# Wiegand.net
KiCad netlist of a schematic drawn in EAGLE
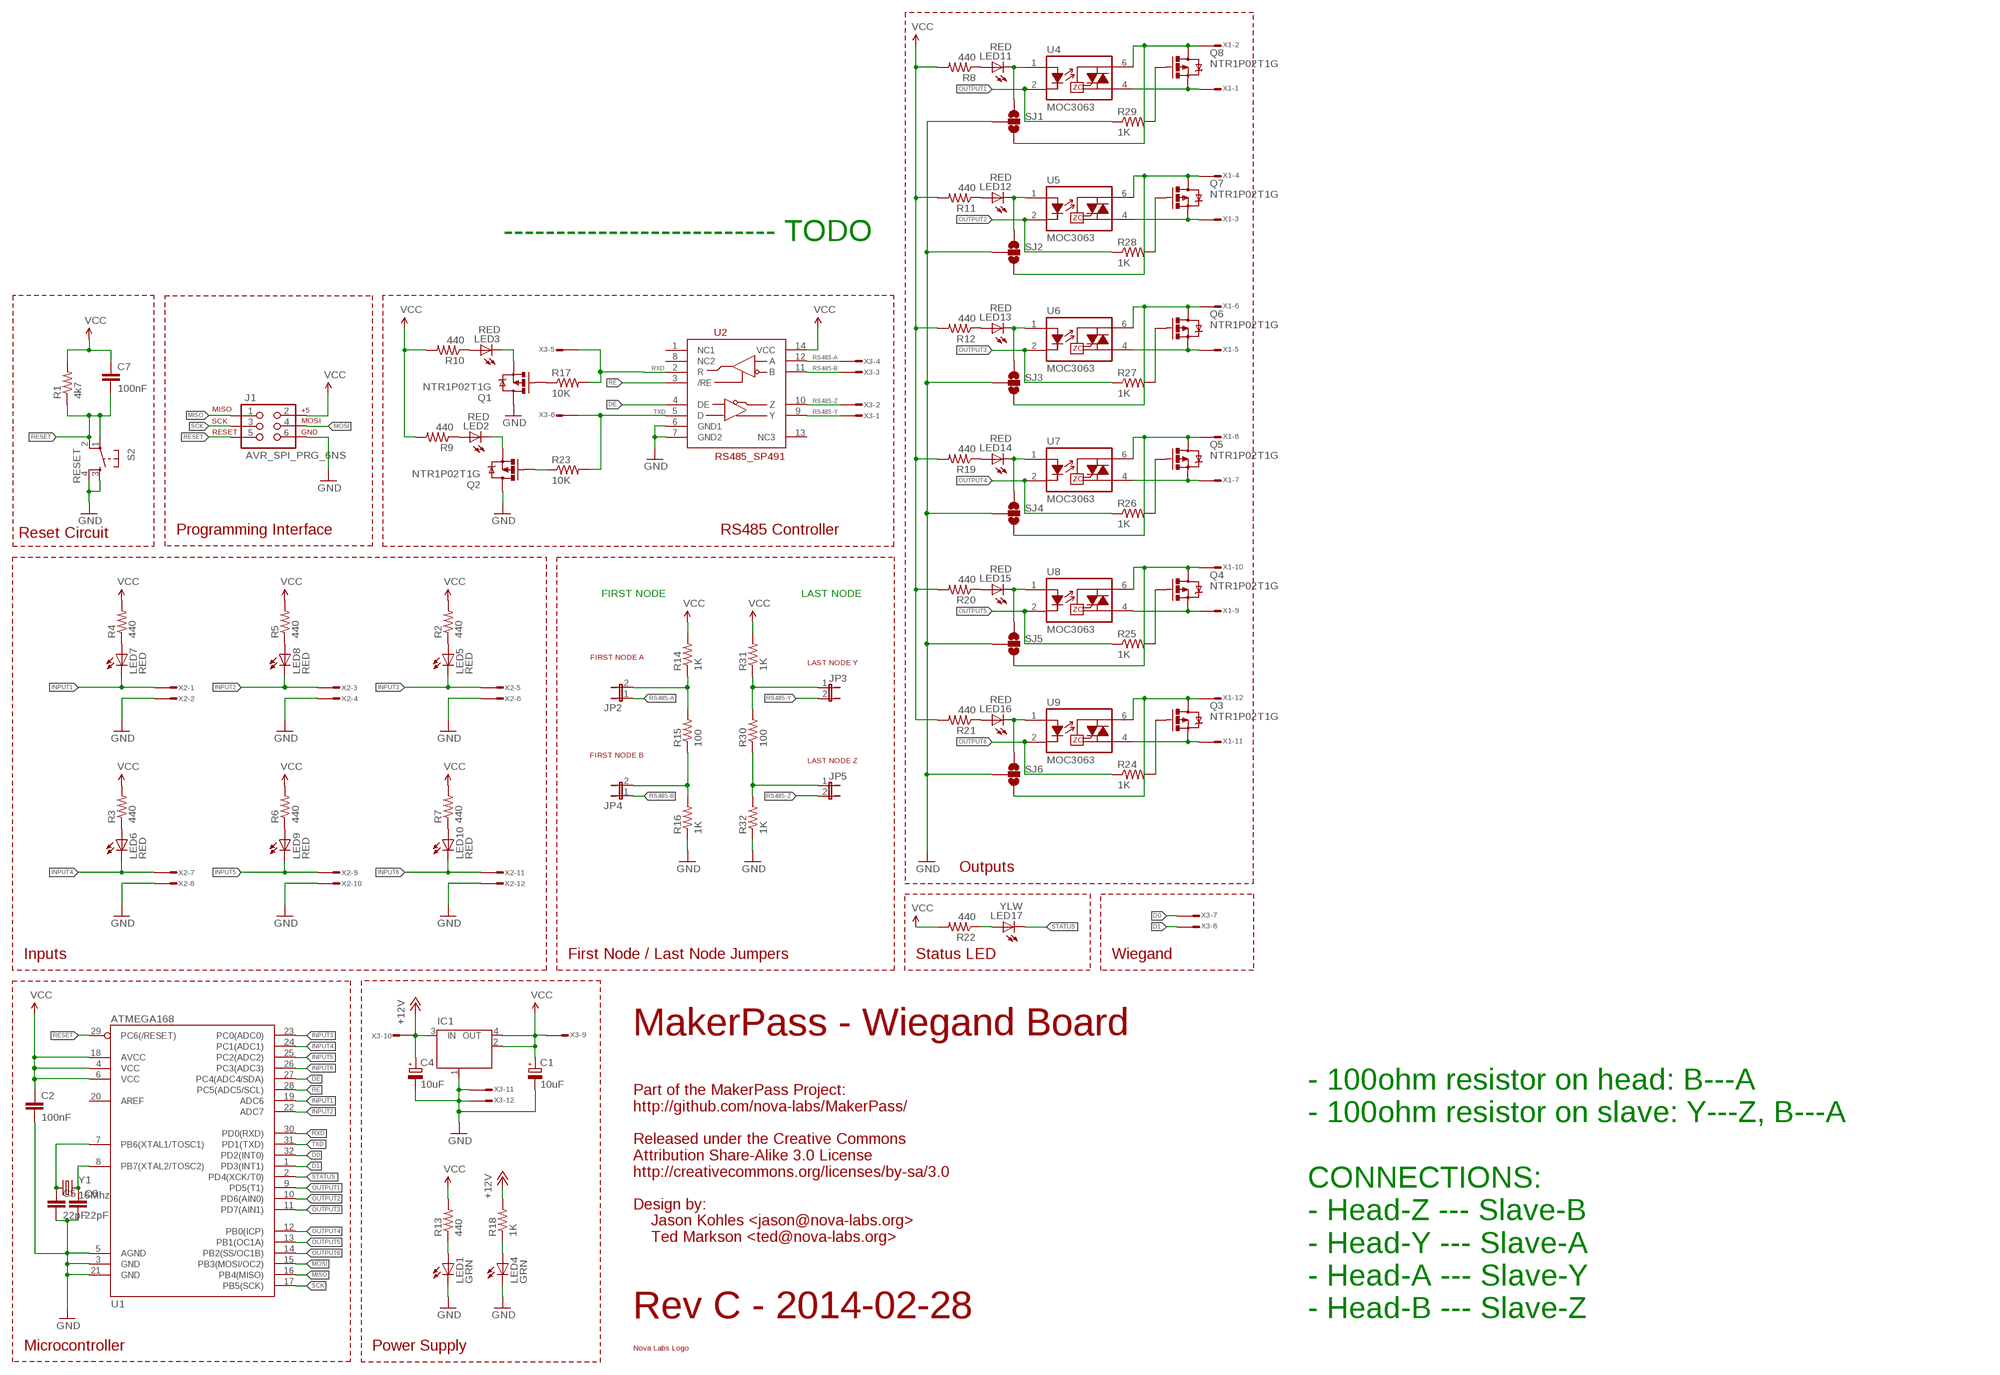
[diagram p0: schematic, sheet 1]

(export (version "E")
  (design (tool "Eeschema 10.0.6"))
  (components
    (comp (ref "C1")
      (value "10uF")
      (footprint "eagle-import:PANASONIC_D")
      (libsource (lib "eagle-import") (part "CPOL-EUD"))
    )
    (comp (ref "C2")
      (value "100nF")
      (footprint "eagle-import:0603-CAP")
      (libsource (lib "eagle-import") (part "CAP0603-CAP"))
    )
    (comp (ref "C4")
      (value "10uF")
      (footprint "eagle-import:PANASONIC_D")
      (libsource (lib "eagle-import") (part "CPOL-EUD"))
    )
    (comp (ref "C5")
      (value "22pF")
      (footprint "eagle-import:0603-CAP")
      (libsource (lib "eagle-import") (part "CAP0603-CAP"))
    )
    (comp (ref "C6")
      (value "22pF")
      (footprint "eagle-import:0603-CAP")
      (libsource (lib "eagle-import") (part "CAP0603-CAP"))
    )
    (comp (ref "C7")
      (value "100nF")
      (footprint "eagle-import:0603-CAP")
      (libsource (lib "eagle-import") (part "CAP0603-CAP"))
    )
    (comp (ref "IC1")
      (value "MC33269ST-3.3T3")
      (footprint "eagle-import:SOT223")
      (libsource (lib "eagle-import") (part "MC33269ST-3.3T3"))
    )
    (comp (ref "J1")
      (value "AVR_SPI_PRG_6NS")
      (footprint "eagle-import:2X3-NS")
      (libsource (lib "eagle-import") (part "AVR_SPI_PRG_6NS"))
    )
    (comp (ref "JP2")
      (value "JUMPER-2PTH")
      (footprint "eagle-import:1X02")
      (libsource (lib "eagle-import") (part "JUMPER-2PTH"))
    )
    (comp (ref "JP3")
      (value "JUMPER-2PTH")
      (footprint "eagle-import:1X02")
      (libsource (lib "eagle-import") (part "JUMPER-2PTH"))
    )
    (comp (ref "JP4")
      (value "JUMPER-2PTH")
      (footprint "eagle-import:1X02")
      (libsource (lib "eagle-import") (part "JUMPER-2PTH"))
    )
    (comp (ref "JP5")
      (value "JUMPER-2PTH")
      (footprint "eagle-import:1X02")
      (libsource (lib "eagle-import") (part "JUMPER-2PTH"))
    )
    (comp (ref "LED1")
      (value "GRN")
      (footprint "eagle-import:LED-805")
      (libsource (lib "eagle-import") (part "LED-0805"))
    )
    (comp (ref "LED2")
      (value "RED")
      (footprint "eagle-import:LED-805")
      (libsource (lib "eagle-import") (part "LED-0805"))
    )
    (comp (ref "LED3")
      (value "RED")
      (footprint "eagle-import:LED-805")
      (libsource (lib "eagle-import") (part "LED-0805"))
    )
    (comp (ref "LED4")
      (value "GRN")
      (footprint "eagle-import:LED-805")
      (libsource (lib "eagle-import") (part "LED-0805"))
    )
    (comp (ref "LED5")
      (value "RED")
      (footprint "eagle-import:LED-805")
      (libsource (lib "eagle-import") (part "LED-0805"))
    )
    (comp (ref "LED6")
      (value "RED")
      (footprint "eagle-import:LED-805")
      (libsource (lib "eagle-import") (part "LED-0805"))
    )
    (comp (ref "LED7")
      (value "RED")
      (footprint "eagle-import:LED-805")
      (libsource (lib "eagle-import") (part "LED-0805"))
    )
    (comp (ref "LED8")
      (value "RED")
      (footprint "eagle-import:LED-805")
      (libsource (lib "eagle-import") (part "LED-0805"))
    )
    (comp (ref "LED9")
      (value "RED")
      (footprint "eagle-import:LED-805")
      (libsource (lib "eagle-import") (part "LED-0805"))
    )
    (comp (ref "LED10")
      (value "RED")
      (footprint "eagle-import:LED-805")
      (libsource (lib "eagle-import") (part "LED-0805"))
    )
    (comp (ref "LED11")
      (value "RED")
      (footprint "eagle-import:LED-805")
      (libsource (lib "eagle-import") (part "LED-0805"))
    )
    (comp (ref "LED12")
      (value "RED")
      (footprint "eagle-import:LED-805")
      (libsource (lib "eagle-import") (part "LED-0805"))
    )
    (comp (ref "LED13")
      (value "RED")
      (footprint "eagle-import:LED-805")
      (libsource (lib "eagle-import") (part "LED-0805"))
    )
    (comp (ref "LED14")
      (value "RED")
      (footprint "eagle-import:LED-805")
      (libsource (lib "eagle-import") (part "LED-0805"))
    )
    (comp (ref "LED15")
      (value "RED")
      (footprint "eagle-import:LED-805")
      (libsource (lib "eagle-import") (part "LED-0805"))
    )
    (comp (ref "LED16")
      (value "RED")
      (footprint "eagle-import:LED-805")
      (libsource (lib "eagle-import") (part "LED-0805"))
    )
    (comp (ref "LED17")
      (value "YLW")
      (footprint "eagle-import:LED-805")
      (libsource (lib "eagle-import") (part "LED-0805"))
    )
    (comp (ref "Q1")
      (value "NTR1P02T1G")
      (footprint "eagle-import:SOT23-3")
      (libsource (lib "eagle-import") (part "MOSFET-PCHANNELSMD"))
    )
    (comp (ref "Q2")
      (value "NTR1P02T1G")
      (footprint "eagle-import:SOT23-3")
      (libsource (lib "eagle-import") (part "MOSFET-PCHANNELSMD"))
    )
    (comp (ref "Q3")
      (value "NTR1P02T1G")
      (footprint "eagle-import:SOT23-3")
      (libsource (lib "eagle-import") (part "MOSFET-PCHANNELSMD"))
    )
    (comp (ref "Q4")
      (value "NTR1P02T1G")
      (footprint "eagle-import:SOT23-3")
      (libsource (lib "eagle-import") (part "MOSFET-PCHANNELSMD"))
    )
    (comp (ref "Q5")
      (value "NTR1P02T1G")
      (footprint "eagle-import:SOT23-3")
      (libsource (lib "eagle-import") (part "MOSFET-PCHANNELSMD"))
    )
    (comp (ref "Q6")
      (value "NTR1P02T1G")
      (footprint "eagle-import:SOT23-3")
      (libsource (lib "eagle-import") (part "MOSFET-PCHANNELSMD"))
    )
    (comp (ref "Q7")
      (value "NTR1P02T1G")
      (footprint "eagle-import:SOT23-3")
      (libsource (lib "eagle-import") (part "MOSFET-PCHANNELSMD"))
    )
    (comp (ref "Q8")
      (value "NTR1P02T1G")
      (footprint "eagle-import:SOT23-3")
      (libsource (lib "eagle-import") (part "MOSFET-PCHANNELSMD"))
    )
    (comp (ref "R1")
      (value "4k7")
      (footprint "eagle-import:0603-RES")
      (libsource (lib "eagle-import") (part "RESISTOR0603-RES"))
    )
    (comp (ref "R2")
      (value "440")
      (footprint "eagle-import:0603-RES")
      (libsource (lib "eagle-import") (part "RESISTOR0603-RES"))
    )
    (comp (ref "R3")
      (value "440")
      (footprint "eagle-import:0603-RES")
      (libsource (lib "eagle-import") (part "RESISTOR0603-RES"))
    )
    (comp (ref "R4")
      (value "440")
      (footprint "eagle-import:0603-RES")
      (libsource (lib "eagle-import") (part "RESISTOR0603-RES"))
    )
    (comp (ref "R5")
      (value "440")
      (footprint "eagle-import:0603-RES")
      (libsource (lib "eagle-import") (part "RESISTOR0603-RES"))
    )
    (comp (ref "R6")
      (value "440")
      (footprint "eagle-import:0603-RES")
      (libsource (lib "eagle-import") (part "RESISTOR0603-RES"))
    )
    (comp (ref "R7")
      (value "440")
      (footprint "eagle-import:0603-RES")
      (libsource (lib "eagle-import") (part "RESISTOR0603-RES"))
    )
    (comp (ref "R8")
      (value "440")
      (footprint "eagle-import:0603-RES")
      (libsource (lib "eagle-import") (part "RESISTOR0603-RES"))
    )
    (comp (ref "R9")
      (value "440")
      (footprint "eagle-import:0603-RES")
      (libsource (lib "eagle-import") (part "RESISTOR0603-RES"))
    )
    (comp (ref "R10")
      (value "440")
      (footprint "eagle-import:0603-RES")
      (libsource (lib "eagle-import") (part "RESISTOR0603-RES"))
    )
    (comp (ref "R11")
      (value "440")
      (footprint "eagle-import:0603-RES")
      (libsource (lib "eagle-import") (part "RESISTOR0603-RES"))
    )
    (comp (ref "R12")
      (value "440")
      (footprint "eagle-import:0603-RES")
      (libsource (lib "eagle-import") (part "RESISTOR0603-RES"))
    )
    (comp (ref "R13")
      (value "440")
      (footprint "eagle-import:0603-RES")
      (libsource (lib "eagle-import") (part "RESISTOR0603-RES"))
    )
    (comp (ref "R14")
      (value "1K")
      (footprint "eagle-import:0603-RES")
      (libsource (lib "eagle-import") (part "RESISTOR0603-RES"))
    )
    (comp (ref "R15")
      (value "100")
      (footprint "eagle-import:0603-RES")
      (libsource (lib "eagle-import") (part "RESISTOR0603-RES"))
    )
    (comp (ref "R16")
      (value "1K")
      (footprint "eagle-import:0603-RES")
      (libsource (lib "eagle-import") (part "RESISTOR0603-RES"))
    )
    (comp (ref "R17")
      (value "10K")
      (footprint "eagle-import:0603-RES")
      (libsource (lib "eagle-import") (part "RESISTOR0603-RES"))
    )
    (comp (ref "R18")
      (value "1K")
      (footprint "eagle-import:0603-RES")
      (libsource (lib "eagle-import") (part "RESISTOR0603-RES"))
    )
    (comp (ref "R19")
      (value "440")
      (footprint "eagle-import:0603-RES")
      (libsource (lib "eagle-import") (part "RESISTOR0603-RES"))
    )
    (comp (ref "R20")
      (value "440")
      (footprint "eagle-import:0603-RES")
      (libsource (lib "eagle-import") (part "RESISTOR0603-RES"))
    )
    (comp (ref "R21")
      (value "440")
      (footprint "eagle-import:0603-RES")
      (libsource (lib "eagle-import") (part "RESISTOR0603-RES"))
    )
    (comp (ref "R22")
      (value "440")
      (footprint "eagle-import:0603-RES")
      (libsource (lib "eagle-import") (part "RESISTOR0603-RES"))
    )
    (comp (ref "R23")
      (value "10K")
      (footprint "eagle-import:0603-RES")
      (libsource (lib "eagle-import") (part "RESISTOR0603-RES"))
    )
    (comp (ref "R24")
      (value "1K")
      (footprint "eagle-import:0603-RES")
      (libsource (lib "eagle-import") (part "RESISTOR0603-RES"))
    )
    (comp (ref "R25")
      (value "1K")
      (footprint "eagle-import:0603-RES")
      (libsource (lib "eagle-import") (part "RESISTOR0603-RES"))
    )
    (comp (ref "R26")
      (value "1K")
      (footprint "eagle-import:0603-RES")
      (libsource (lib "eagle-import") (part "RESISTOR0603-RES"))
    )
    (comp (ref "R27")
      (value "1K")
      (footprint "eagle-import:0603-RES")
      (libsource (lib "eagle-import") (part "RESISTOR0603-RES"))
    )
    (comp (ref "R28")
      (value "1K")
      (footprint "eagle-import:0603-RES")
      (libsource (lib "eagle-import") (part "RESISTOR0603-RES"))
    )
    (comp (ref "R29")
      (value "1K")
      (footprint "eagle-import:0603-RES")
      (libsource (lib "eagle-import") (part "RESISTOR0603-RES"))
    )
    (comp (ref "R30")
      (value "100")
      (footprint "eagle-import:0603-RES")
      (libsource (lib "eagle-import") (part "RESISTOR0603-RES"))
    )
    (comp (ref "R31")
      (value "1K")
      (footprint "eagle-import:0603-RES")
      (libsource (lib "eagle-import") (part "RESISTOR0603-RES"))
    )
    (comp (ref "R32")
      (value "1K")
      (footprint "eagle-import:0603-RES")
      (libsource (lib "eagle-import") (part "RESISTOR0603-RES"))
    )
    (comp (ref "S2")
      (value "RESET")
      (footprint "eagle-import:TACTILE_SWITCH_SMD")
      (libsource (lib "eagle-import") (part "TAC_SWITCHSMD"))
    )
    (comp (ref "SJ1")
      (value "SOLDERJUMPER_2WAY-TRACE1&2&3")
      (footprint "eagle-import:SJ_3_WIRE1&2&3")
      (libsource (lib "eagle-import") (part "SOLDERJUMPER_2WAY-TRACE1&2&3"))
    )
    (comp (ref "SJ2")
      (value "SOLDERJUMPER_2WAY-TRACE1&2&3")
      (footprint "eagle-import:SJ_3_WIRE1&2&3")
      (libsource (lib "eagle-import") (part "SOLDERJUMPER_2WAY-TRACE1&2&3"))
    )
    (comp (ref "SJ3")
      (value "SOLDERJUMPER_2WAY-TRACE1&2&3")
      (footprint "eagle-import:SJ_3_WIRE1&2&3")
      (libsource (lib "eagle-import") (part "SOLDERJUMPER_2WAY-TRACE1&2&3"))
    )
    (comp (ref "SJ4")
      (value "SOLDERJUMPER_2WAY-TRACE1&2&3")
      (footprint "eagle-import:SJ_3_WIRE1&2&3")
      (libsource (lib "eagle-import") (part "SOLDERJUMPER_2WAY-TRACE1&2&3"))
    )
    (comp (ref "SJ5")
      (value "SOLDERJUMPER_2WAY-TRACE1&2&3")
      (footprint "eagle-import:SJ_3_WIRE1&2&3")
      (libsource (lib "eagle-import") (part "SOLDERJUMPER_2WAY-TRACE1&2&3"))
    )
    (comp (ref "SJ6")
      (value "SOLDERJUMPER_2WAY-TRACE1&2&3")
      (footprint "eagle-import:SJ_3_WIRE1&2&3")
      (libsource (lib "eagle-import") (part "SOLDERJUMPER_2WAY-TRACE1&2&3"))
    )
    (comp (ref "U1")
      (value "ATMEGA168")
      (footprint "eagle-import:TQFP32-08")
      (libsource (lib "eagle-import") (part "ATMEGA168"))
    )
    (comp (ref "U2")
      (value "RS485_SP491")
      (footprint "eagle-import:SOIC-14")
      (libsource (lib "eagle-import") (part "RS485_SP491"))
    )
    (comp (ref "U4")
      (value "MOC3063")
      (footprint "eagle-import:DIP8SMD")
      (libsource (lib "eagle-import") (part "MOC3063S"))
    )
    (comp (ref "U5")
      (value "MOC3063")
      (footprint "eagle-import:DIP8SMD")
      (libsource (lib "eagle-import") (part "MOC3063S"))
    )
    (comp (ref "U6")
      (value "MOC3063")
      (footprint "eagle-import:DIP8SMD")
      (libsource (lib "eagle-import") (part "MOC3063S"))
    )
    (comp (ref "U7")
      (value "MOC3063")
      (footprint "eagle-import:DIP8SMD")
      (libsource (lib "eagle-import") (part "MOC3063S"))
    )
    (comp (ref "U8")
      (value "MOC3063")
      (footprint "eagle-import:DIP8SMD")
      (libsource (lib "eagle-import") (part "MOC3063S"))
    )
    (comp (ref "U9")
      (value "MOC3063")
      (footprint "eagle-import:DIP8SMD")
      (libsource (lib "eagle-import") (part "MOC3063S"))
    )
    (comp (ref "X1")
      (value "CON-1X12-TERMBLOCK-3.5MM")
      (footprint "eagle-import:CON-1X12-TERMBLOCK-3.5MM")
      (fields (field (name "MFG_PN") "OSTTE120104"))
      (libsource (lib "eagle-import") (part "CON-1X12-TERMBLOCK-3.5MM"))
    )
    (comp (ref "X2")
      (value "CON-1X12-TERMBLOCK-3.5MM")
      (footprint "eagle-import:CON-1X12-TERMBLOCK-3.5MM")
      (fields (field (name "MFG_PN") "OSTTE120104"))
      (libsource (lib "eagle-import") (part "CON-1X12-TERMBLOCK-3.5MM"))
    )
    (comp (ref "X3")
      (value "CON-1X12-TERMBLOCK-3.5MM")
      (footprint "eagle-import:CON-1X12-TERMBLOCK-3.5MM")
      (fields (field (name "MFG_PN") "OSTTE120104"))
      (libsource (lib "eagle-import") (part "CON-1X12-TERMBLOCK-3.5MM"))
    )
    (comp (ref "X4")
      (value "NOVA-LABS-LOGO-SILK-400MIL")
      (footprint "eagle-import:NOVA-LABS-LOGO-SILK-400MIL")
      (libsource (lib "eagle-import") (part "NOVA-LABS-LOGO-SILK-400MIL"))
    )
    (comp (ref "Y1")
      (value "16Mhz")
      (footprint "eagle-import:HC49UP")
      (libsource (lib "eagle-import") (part "CRYSTALSMD"))
    )
  )
  (nets
    (net (code "1") (name "+12V") (class "Default")
      (node (ref "C4") (pin "+") (pinfunction "+_+") (pintype "passive"))
      (node (ref "IC1") (pin "3") (pinfunction "IN_3") (pintype "input"))
      (node (ref "R18") (pin "2") (pinfunction "2_2") (pintype "passive"))
      (node (ref "X3") (pin "10") (pinfunction "S_10") (pintype "passive"))
    )
    (net (code "2") (name "D0") (class "Default")
      (node (ref "U1") (pin "32") (pinfunction "PD2(INT0)_32") (pintype "bidirectional"))
      (node (ref "X3") (pin "7") (pinfunction "S_7") (pintype "passive"))
    )
    (net (code "3") (name "D1") (class "Default")
      (node (ref "U1") (pin "1") (pinfunction "PD3(INT1)_1") (pintype "bidirectional"))
      (node (ref "X3") (pin "8") (pinfunction "S_8") (pintype "passive"))
    )
    (net (code "4") (name "DE") (class "Default")
      (node (ref "U1") (pin "27") (pinfunction "PC4(ADC4/SDA)_27") (pintype "bidirectional"))
      (node (ref "U2") (pin "4") (pinfunction "DE_4") (pintype "bidirectional"))
    )
    (net (code "5") (name "GND") (class "Default")
      (node (ref "C1") (pin "-") (pinfunction "-_-") (pintype "passive"))
      (node (ref "C2") (pin "2") (pinfunction "2_2") (pintype "passive"))
      (node (ref "C4") (pin "-") (pinfunction "-_-") (pintype "passive"))
      (node (ref "C5") (pin "2") (pinfunction "2_2") (pintype "passive"))
      (node (ref "C6") (pin "2") (pinfunction "2_2") (pintype "passive"))
      (node (ref "IC1") (pin "1") (pinfunction "GND/ADJ_1") (pintype "input"))
      (node (ref "J1") (pin "6") (pinfunction "6_6") (pintype "passive"))
      (node (ref "LED1") (pin "C") (pinfunction "C_C") (pintype "passive"))
      (node (ref "LED4") (pin "C") (pinfunction "C_C") (pintype "passive"))
      (node (ref "Q1") (pin "3") (pinfunction "D_3") (pintype "passive"))
      (node (ref "Q2") (pin "3") (pinfunction "D_3") (pintype "passive"))
      (node (ref "R16") (pin "1") (pinfunction "1_1") (pintype "passive"))
      (node (ref "R32") (pin "1") (pinfunction "1_1") (pintype "passive"))
      (node (ref "S2") (pin "3") (pinfunction "3_3") (pintype "passive"))
      (node (ref "S2") (pin "4") (pinfunction "4_4") (pintype "passive"))
      (node (ref "SJ1") (pin "2") (pinfunction "2_2") (pintype "passive"))
      (node (ref "SJ2") (pin "2") (pinfunction "2_2") (pintype "passive"))
      (node (ref "SJ3") (pin "2") (pinfunction "2_2") (pintype "passive"))
      (node (ref "SJ4") (pin "2") (pinfunction "2_2") (pintype "passive"))
      (node (ref "SJ5") (pin "2") (pinfunction "2_2") (pintype "passive"))
      (node (ref "SJ6") (pin "2") (pinfunction "2_2") (pintype "passive"))
      (node (ref "U1") (pin "21") (pinfunction "GND_21") (pintype "bidirectional"))
      (node (ref "U1") (pin "3") (pinfunction "GND_3") (pintype "bidirectional"))
      (node (ref "U1") (pin "5") (pinfunction "AGND_5") (pintype "bidirectional"))
      (node (ref "U2") (pin "6") (pinfunction "GND1_6") (pintype "bidirectional"))
      (node (ref "U2") (pin "7") (pinfunction "GND2_7") (pintype "bidirectional"))
      (node (ref "X2") (pin "10") (pinfunction "S_10") (pintype "passive"))
      (node (ref "X2") (pin "12") (pinfunction "S_12") (pintype "passive"))
      (node (ref "X2") (pin "2") (pinfunction "S_2") (pintype "passive"))
      (node (ref "X2") (pin "4") (pinfunction "S_4") (pintype "passive"))
      (node (ref "X2") (pin "6") (pinfunction "S_6") (pintype "passive"))
      (node (ref "X2") (pin "8") (pinfunction "S_8") (pintype "passive"))
      (node (ref "X3") (pin "11") (pinfunction "S_11") (pintype "passive"))
      (node (ref "X3") (pin "12") (pinfunction "S_12") (pintype "passive"))
    )
    (net (code "6") (name "INPUT1") (class "Default")
      (node (ref "LED7") (pin "C") (pinfunction "C_C") (pintype "passive"))
      (node (ref "U1") (pin "19") (pinfunction "ADC6_19") (pintype "bidirectional"))
      (node (ref "X2") (pin "1") (pinfunction "S_1") (pintype "passive"))
    )
    (net (code "7") (name "INPUT2") (class "Default")
      (node (ref "LED8") (pin "C") (pinfunction "C_C") (pintype "passive"))
      (node (ref "U1") (pin "22") (pinfunction "ADC7_22") (pintype "bidirectional"))
      (node (ref "X2") (pin "3") (pinfunction "S_3") (pintype "passive"))
    )
    (net (code "8") (name "INPUT3") (class "Default")
      (node (ref "LED5") (pin "C") (pinfunction "C_C") (pintype "passive"))
      (node (ref "U1") (pin "23") (pinfunction "PC0(ADC0)_23") (pintype "bidirectional"))
      (node (ref "X2") (pin "5") (pinfunction "S_5") (pintype "passive"))
    )
    (net (code "9") (name "INPUT4") (class "Default")
      (node (ref "LED6") (pin "C") (pinfunction "C_C") (pintype "passive"))
      (node (ref "U1") (pin "24") (pinfunction "PC1(ADC1)_24") (pintype "bidirectional"))
      (node (ref "X2") (pin "7") (pinfunction "S_7") (pintype "passive"))
    )
    (net (code "10") (name "INPUT5") (class "Default")
      (node (ref "LED9") (pin "C") (pinfunction "C_C") (pintype "passive"))
      (node (ref "U1") (pin "25") (pinfunction "PC2(ADC2)_25") (pintype "bidirectional"))
      (node (ref "X2") (pin "9") (pinfunction "S_9") (pintype "passive"))
    )
    (net (code "11") (name "INPUT6") (class "Default")
      (node (ref "LED10") (pin "C") (pinfunction "C_C") (pintype "passive"))
      (node (ref "U1") (pin "26") (pinfunction "PC3(ADC3)_26") (pintype "bidirectional"))
      (node (ref "X2") (pin "11") (pinfunction "S_11") (pintype "passive"))
    )
    (net (code "12") (name "MISO") (class "Default")
      (node (ref "J1") (pin "1") (pinfunction "1_1") (pintype "passive"))
      (node (ref "U1") (pin "16") (pinfunction "PB4(MISO)_16") (pintype "bidirectional"))
    )
    (net (code "13") (name "MOSI") (class "Default")
      (node (ref "J1") (pin "4") (pinfunction "4_4") (pintype "passive"))
      (node (ref "U1") (pin "15") (pinfunction "PB3(MOSI/OC2)_15") (pintype "bidirectional"))
    )
    (net (code "14") (name "Net-(JP2-Pad2)") (class "Default")
      (node (ref "JP2") (pin "2") (pinfunction "2_2") (pintype "passive"))
      (node (ref "R14") (pin "1") (pinfunction "1_1") (pintype "passive"))
      (node (ref "R15") (pin "2") (pinfunction "2_2") (pintype "passive"))
    )
    (net (code "15") (name "Net-(JP3-Pad1)") (class "Default")
      (node (ref "JP3") (pin "1") (pinfunction "1_1") (pintype "passive"))
      (node (ref "R30") (pin "2") (pinfunction "2_2") (pintype "passive"))
      (node (ref "R31") (pin "1") (pinfunction "1_1") (pintype "passive"))
    )
    (net (code "16") (name "Net-(JP4-Pad2)") (class "Default")
      (node (ref "JP4") (pin "2") (pinfunction "2_2") (pintype "passive"))
      (node (ref "R15") (pin "1") (pinfunction "1_1") (pintype "passive"))
      (node (ref "R16") (pin "2") (pinfunction "2_2") (pintype "passive"))
    )
    (net (code "17") (name "Net-(JP5-Pad1)") (class "Default")
      (node (ref "JP5") (pin "1") (pinfunction "1_1") (pintype "passive"))
      (node (ref "R30") (pin "1") (pinfunction "1_1") (pintype "passive"))
      (node (ref "R32") (pin "2") (pinfunction "2_2") (pintype "passive"))
    )
    (net (code "18") (name "Net-(LED1-PadA)") (class "Default")
      (node (ref "LED1") (pin "A") (pinfunction "A_A") (pintype "passive"))
      (node (ref "R13") (pin "1") (pinfunction "1_1") (pintype "passive"))
    )
    (net (code "19") (name "Net-(LED2-PadA)") (class "Default")
      (node (ref "LED2") (pin "A") (pinfunction "A_A") (pintype "passive"))
      (node (ref "R9") (pin "1") (pinfunction "1_1") (pintype "passive"))
    )
    (net (code "20") (name "Net-(LED3-PadA)") (class "Default")
      (node (ref "LED3") (pin "A") (pinfunction "A_A") (pintype "passive"))
      (node (ref "R10") (pin "1") (pinfunction "1_1") (pintype "passive"))
    )
    (net (code "21") (name "Net-(LED4-PadA)") (class "Default")
      (node (ref "LED4") (pin "A") (pinfunction "A_A") (pintype "passive"))
      (node (ref "R18") (pin "1") (pinfunction "1_1") (pintype "passive"))
    )
    (net (code "22") (name "Net-(LED5-PadA)") (class "Default")
      (node (ref "LED5") (pin "A") (pinfunction "A_A") (pintype "passive"))
      (node (ref "R2") (pin "1") (pinfunction "1_1") (pintype "passive"))
    )
    (net (code "23") (name "Net-(LED6-PadA)") (class "Default")
      (node (ref "LED6") (pin "A") (pinfunction "A_A") (pintype "passive"))
      (node (ref "R3") (pin "1") (pinfunction "1_1") (pintype "passive"))
    )
    (net (code "24") (name "Net-(LED7-PadA)") (class "Default")
      (node (ref "LED7") (pin "A") (pinfunction "A_A") (pintype "passive"))
      (node (ref "R4") (pin "1") (pinfunction "1_1") (pintype "passive"))
    )
    (net (code "25") (name "Net-(LED8-PadA)") (class "Default")
      (node (ref "LED8") (pin "A") (pinfunction "A_A") (pintype "passive"))
      (node (ref "R5") (pin "1") (pinfunction "1_1") (pintype "passive"))
    )
    (net (code "26") (name "Net-(LED9-PadA)") (class "Default")
      (node (ref "LED9") (pin "A") (pinfunction "A_A") (pintype "passive"))
      (node (ref "R6") (pin "1") (pinfunction "1_1") (pintype "passive"))
    )
    (net (code "27") (name "Net-(LED10-PadA)") (class "Default")
      (node (ref "LED10") (pin "A") (pinfunction "A_A") (pintype "passive"))
      (node (ref "R7") (pin "1") (pinfunction "1_1") (pintype "passive"))
    )
    (net (code "28") (name "Net-(LED11-PadA)") (class "Default")
      (node (ref "LED11") (pin "A") (pinfunction "A_A") (pintype "passive"))
      (node (ref "R8") (pin "1") (pinfunction "1_1") (pintype "passive"))
    )
    (net (code "29") (name "Net-(LED12-PadA)") (class "Default")
      (node (ref "LED12") (pin "A") (pinfunction "A_A") (pintype "passive"))
      (node (ref "R11") (pin "1") (pinfunction "1_1") (pintype "passive"))
    )
    (net (code "30") (name "Net-(LED13-PadA)") (class "Default")
      (node (ref "LED13") (pin "A") (pinfunction "A_A") (pintype "passive"))
      (node (ref "R12") (pin "1") (pinfunction "1_1") (pintype "passive"))
    )
    (net (code "31") (name "Net-(LED14-PadA)") (class "Default")
      (node (ref "LED14") (pin "A") (pinfunction "A_A") (pintype "passive"))
      (node (ref "R19") (pin "1") (pinfunction "1_1") (pintype "passive"))
    )
    (net (code "32") (name "Net-(LED15-PadA)") (class "Default")
      (node (ref "LED15") (pin "A") (pinfunction "A_A") (pintype "passive"))
      (node (ref "R20") (pin "1") (pinfunction "1_1") (pintype "passive"))
    )
    (net (code "33") (name "Net-(LED16-PadA)") (class "Default")
      (node (ref "LED16") (pin "A") (pinfunction "A_A") (pintype "passive"))
      (node (ref "R21") (pin "1") (pinfunction "1_1") (pintype "passive"))
    )
    (net (code "34") (name "Net-(LED17-PadA)") (class "Default")
      (node (ref "LED17") (pin "A") (pinfunction "A_A") (pintype "passive"))
      (node (ref "R22") (pin "1") (pinfunction "1_1") (pintype "passive"))
    )
    (net (code "35") (name "Net-(Q1-G)") (class "Default")
      (node (ref "Q1") (pin "1") (pinfunction "G_1") (pintype "passive"))
      (node (ref "R17") (pin "1") (pinfunction "1_1") (pintype "passive"))
    )
    (net (code "36") (name "Net-(Q1-S)") (class "Default")
      (node (ref "LED3") (pin "C") (pinfunction "C_C") (pintype "passive"))
      (node (ref "Q1") (pin "2") (pinfunction "S_2") (pintype "passive"))
    )
    (net (code "37") (name "Net-(Q2-G)") (class "Default")
      (node (ref "Q2") (pin "1") (pinfunction "G_1") (pintype "passive"))
      (node (ref "R23") (pin "1") (pinfunction "1_1") (pintype "passive"))
    )
    (net (code "38") (name "Net-(Q2-S)") (class "Default")
      (node (ref "LED2") (pin "C") (pinfunction "C_C") (pintype "passive"))
      (node (ref "Q2") (pin "2") (pinfunction "S_2") (pintype "passive"))
    )
    (net (code "39") (name "Net-(Q3-D)") (class "Default")
      (node (ref "Q3") (pin "3") (pinfunction "D_3") (pintype "passive"))
      (node (ref "SJ6") (pin "3") (pinfunction "3_3") (pintype "passive"))
      (node (ref "U9") (pin "6") (pinfunction "T1_6") (pintype "bidirectional"))
      (node (ref "X1") (pin "12") (pinfunction "S_12") (pintype "passive"))
    )
    (net (code "40") (name "Net-(Q3-G)") (class "Default")
      (node (ref "Q3") (pin "1") (pinfunction "G_1") (pintype "passive"))
      (node (ref "R24") (pin "2") (pinfunction "2_2") (pintype "passive"))
    )
    (net (code "41") (name "Net-(Q3-S)") (class "Default")
      (node (ref "Q3") (pin "2") (pinfunction "S_2") (pintype "passive"))
      (node (ref "U9") (pin "4") (pinfunction "T2_4") (pintype "bidirectional"))
      (node (ref "X1") (pin "11") (pinfunction "S_11") (pintype "passive"))
    )
    (net (code "42") (name "Net-(Q4-D)") (class "Default")
      (node (ref "Q4") (pin "3") (pinfunction "D_3") (pintype "passive"))
      (node (ref "SJ5") (pin "3") (pinfunction "3_3") (pintype "passive"))
      (node (ref "U8") (pin "6") (pinfunction "T1_6") (pintype "bidirectional"))
      (node (ref "X1") (pin "10") (pinfunction "S_10") (pintype "passive"))
    )
    (net (code "43") (name "Net-(Q4-G)") (class "Default")
      (node (ref "Q4") (pin "1") (pinfunction "G_1") (pintype "passive"))
      (node (ref "R25") (pin "2") (pinfunction "2_2") (pintype "passive"))
    )
    (net (code "44") (name "Net-(Q4-S)") (class "Default")
      (node (ref "Q4") (pin "2") (pinfunction "S_2") (pintype "passive"))
      (node (ref "U8") (pin "4") (pinfunction "T2_4") (pintype "bidirectional"))
      (node (ref "X1") (pin "9") (pinfunction "S_9") (pintype "passive"))
    )
    (net (code "45") (name "Net-(Q5-D)") (class "Default")
      (node (ref "Q5") (pin "3") (pinfunction "D_3") (pintype "passive"))
      (node (ref "SJ4") (pin "3") (pinfunction "3_3") (pintype "passive"))
      (node (ref "U7") (pin "6") (pinfunction "T1_6") (pintype "bidirectional"))
      (node (ref "X1") (pin "8") (pinfunction "S_8") (pintype "passive"))
    )
    (net (code "46") (name "Net-(Q5-G)") (class "Default")
      (node (ref "Q5") (pin "1") (pinfunction "G_1") (pintype "passive"))
      (node (ref "R26") (pin "2") (pinfunction "2_2") (pintype "passive"))
    )
    (net (code "47") (name "Net-(Q5-S)") (class "Default")
      (node (ref "Q5") (pin "2") (pinfunction "S_2") (pintype "passive"))
      (node (ref "U7") (pin "4") (pinfunction "T2_4") (pintype "bidirectional"))
      (node (ref "X1") (pin "7") (pinfunction "S_7") (pintype "passive"))
    )
    (net (code "48") (name "Net-(Q6-D)") (class "Default")
      (node (ref "Q6") (pin "3") (pinfunction "D_3") (pintype "passive"))
      (node (ref "SJ3") (pin "3") (pinfunction "3_3") (pintype "passive"))
      (node (ref "U6") (pin "6") (pinfunction "T1_6") (pintype "bidirectional"))
      (node (ref "X1") (pin "6") (pinfunction "S_6") (pintype "passive"))
    )
    (net (code "49") (name "Net-(Q6-G)") (class "Default")
      (node (ref "Q6") (pin "1") (pinfunction "G_1") (pintype "passive"))
      (node (ref "R27") (pin "2") (pinfunction "2_2") (pintype "passive"))
    )
    (net (code "50") (name "Net-(Q6-S)") (class "Default")
      (node (ref "Q6") (pin "2") (pinfunction "S_2") (pintype "passive"))
      (node (ref "U6") (pin "4") (pinfunction "T2_4") (pintype "bidirectional"))
      (node (ref "X1") (pin "5") (pinfunction "S_5") (pintype "passive"))
    )
    (net (code "51") (name "Net-(Q7-D)") (class "Default")
      (node (ref "Q7") (pin "3") (pinfunction "D_3") (pintype "passive"))
      (node (ref "SJ2") (pin "3") (pinfunction "3_3") (pintype "passive"))
      (node (ref "U5") (pin "6") (pinfunction "T1_6") (pintype "bidirectional"))
      (node (ref "X1") (pin "4") (pinfunction "S_4") (pintype "passive"))
    )
    (net (code "52") (name "Net-(Q7-G)") (class "Default")
      (node (ref "Q7") (pin "1") (pinfunction "G_1") (pintype "passive"))
      (node (ref "R28") (pin "2") (pinfunction "2_2") (pintype "passive"))
    )
    (net (code "53") (name "Net-(Q7-S)") (class "Default")
      (node (ref "Q7") (pin "2") (pinfunction "S_2") (pintype "passive"))
      (node (ref "U5") (pin "4") (pinfunction "T2_4") (pintype "bidirectional"))
      (node (ref "X1") (pin "3") (pinfunction "S_3") (pintype "passive"))
    )
    (net (code "54") (name "Net-(Q8-D)") (class "Default")
      (node (ref "Q8") (pin "3") (pinfunction "D_3") (pintype "passive"))
      (node (ref "SJ1") (pin "3") (pinfunction "3_3") (pintype "passive"))
      (node (ref "U4") (pin "6") (pinfunction "T1_6") (pintype "bidirectional"))
      (node (ref "X1") (pin "2") (pinfunction "S_2") (pintype "passive"))
    )
    (net (code "55") (name "Net-(Q8-G)") (class "Default")
      (node (ref "Q8") (pin "1") (pinfunction "G_1") (pintype "passive"))
      (node (ref "R29") (pin "2") (pinfunction "2_2") (pintype "passive"))
    )
    (net (code "56") (name "Net-(Q8-S)") (class "Default")
      (node (ref "Q8") (pin "2") (pinfunction "S_2") (pintype "passive"))
      (node (ref "U4") (pin "4") (pinfunction "T2_4") (pintype "bidirectional"))
      (node (ref "X1") (pin "1") (pinfunction "S_1") (pintype "passive"))
    )
    (net (code "57") (name "Net-(U1-PB6(XTAL1{slash}TOSC1))") (class "Default")
      (node (ref "C5") (pin "1") (pinfunction "1_1") (pintype "passive"))
      (node (ref "U1") (pin "7") (pinfunction "PB6(XTAL1/TOSC1)_7") (pintype "bidirectional"))
      (node (ref "Y1") (pin "1") (pinfunction "1_1") (pintype "passive"))
    )
    (net (code "58") (name "Net-(U1-PB7(XTAL2{slash}TOSC2))") (class "Default")
      (node (ref "C6") (pin "1") (pinfunction "1_1") (pintype "passive"))
      (node (ref "U1") (pin "8") (pinfunction "PB7(XTAL2/TOSC2)_8") (pintype "bidirectional"))
      (node (ref "Y1") (pin "2") (pinfunction "2_2") (pintype "passive"))
    )
    (net (code "59") (name "Net-(U4-A)") (class "Default")
      (node (ref "LED11") (pin "C") (pinfunction "C_C") (pintype "passive"))
      (node (ref "SJ1") (pin "1") (pinfunction "1_1") (pintype "passive"))
      (node (ref "U4") (pin "1") (pinfunction "A_1") (pintype "bidirectional"))
    )
    (net (code "60") (name "Net-(U5-A)") (class "Default")
      (node (ref "LED12") (pin "C") (pinfunction "C_C") (pintype "passive"))
      (node (ref "SJ2") (pin "1") (pinfunction "1_1") (pintype "passive"))
      (node (ref "U5") (pin "1") (pinfunction "A_1") (pintype "bidirectional"))
    )
    (net (code "61") (name "Net-(U6-A)") (class "Default")
      (node (ref "LED13") (pin "C") (pinfunction "C_C") (pintype "passive"))
      (node (ref "SJ3") (pin "1") (pinfunction "1_1") (pintype "passive"))
      (node (ref "U6") (pin "1") (pinfunction "A_1") (pintype "bidirectional"))
    )
    (net (code "62") (name "Net-(U7-A)") (class "Default")
      (node (ref "LED14") (pin "C") (pinfunction "C_C") (pintype "passive"))
      (node (ref "SJ4") (pin "1") (pinfunction "1_1") (pintype "passive"))
      (node (ref "U7") (pin "1") (pinfunction "A_1") (pintype "bidirectional"))
    )
    (net (code "63") (name "Net-(U8-A)") (class "Default")
      (node (ref "LED15") (pin "C") (pinfunction "C_C") (pintype "passive"))
      (node (ref "SJ5") (pin "1") (pinfunction "1_1") (pintype "passive"))
      (node (ref "U8") (pin "1") (pinfunction "A_1") (pintype "bidirectional"))
    )
    (net (code "64") (name "Net-(U9-A)") (class "Default")
      (node (ref "LED16") (pin "C") (pinfunction "C_C") (pintype "passive"))
      (node (ref "SJ6") (pin "1") (pinfunction "1_1") (pintype "passive"))
      (node (ref "U9") (pin "1") (pinfunction "A_1") (pintype "bidirectional"))
    )
    (net (code "65") (name "OUTPUT1") (class "Default")
      (node (ref "R29") (pin "1") (pinfunction "1_1") (pintype "passive"))
      (node (ref "U1") (pin "9") (pinfunction "PD5(T1)_9") (pintype "bidirectional"))
      (node (ref "U4") (pin "2") (pinfunction "K_2") (pintype "bidirectional"))
    )
    (net (code "66") (name "OUTPUT2") (class "Default")
      (node (ref "R28") (pin "1") (pinfunction "1_1") (pintype "passive"))
      (node (ref "U1") (pin "10") (pinfunction "PD6(AIN0)_10") (pintype "bidirectional"))
      (node (ref "U5") (pin "2") (pinfunction "K_2") (pintype "bidirectional"))
    )
    (net (code "67") (name "OUTPUT3") (class "Default")
      (node (ref "R27") (pin "1") (pinfunction "1_1") (pintype "passive"))
      (node (ref "U1") (pin "11") (pinfunction "PD7(AIN1)_11") (pintype "bidirectional"))
      (node (ref "U6") (pin "2") (pinfunction "K_2") (pintype "bidirectional"))
    )
    (net (code "68") (name "OUTPUT4") (class "Default")
      (node (ref "R26") (pin "1") (pinfunction "1_1") (pintype "passive"))
      (node (ref "U1") (pin "12") (pinfunction "PB0(ICP)_12") (pintype "bidirectional"))
      (node (ref "U7") (pin "2") (pinfunction "K_2") (pintype "bidirectional"))
    )
    (net (code "69") (name "OUTPUT5") (class "Default")
      (node (ref "R25") (pin "1") (pinfunction "1_1") (pintype "passive"))
      (node (ref "U1") (pin "13") (pinfunction "PB1(OC1A)_13") (pintype "bidirectional"))
      (node (ref "U8") (pin "2") (pinfunction "K_2") (pintype "bidirectional"))
    )
    (net (code "70") (name "OUTPUT6") (class "Default")
      (node (ref "R24") (pin "1") (pinfunction "1_1") (pintype "passive"))
      (node (ref "U1") (pin "14") (pinfunction "PB2(SS/OC1B)_14") (pintype "bidirectional"))
      (node (ref "U9") (pin "2") (pinfunction "K_2") (pintype "bidirectional"))
    )
    (net (code "71") (name "RE") (class "Default")
      (node (ref "U1") (pin "28") (pinfunction "PC5(ADC5/SCL)_28") (pintype "bidirectional"))
      (node (ref "U2") (pin "3") (pinfunction "/RE_3") (pintype "bidirectional"))
    )
    (net (code "72") (name "RESET") (class "Default")
      (node (ref "C7") (pin "2") (pinfunction "2_2") (pintype "passive"))
      (node (ref "J1") (pin "5") (pinfunction "5_5") (pintype "passive"))
      (node (ref "R1") (pin "1") (pinfunction "1_1") (pintype "passive"))
      (node (ref "S2") (pin "1") (pinfunction "1_1") (pintype "passive"))
      (node (ref "S2") (pin "2") (pinfunction "2_2") (pintype "passive"))
      (node (ref "U1") (pin "29") (pinfunction "PC6(/RESET)_29") (pintype "bidirectional"))
    )
    (net (code "73") (name "RS485-A") (class "Default")
      (node (ref "JP2") (pin "1") (pinfunction "1_1") (pintype "passive"))
      (node (ref "U2") (pin "12") (pinfunction "A_12") (pintype "bidirectional"))
      (node (ref "X3") (pin "4") (pinfunction "S_4") (pintype "passive"))
    )
    (net (code "74") (name "RS485-B") (class "Default")
      (node (ref "JP4") (pin "1") (pinfunction "1_1") (pintype "passive"))
      (node (ref "U2") (pin "11") (pinfunction "B_11") (pintype "bidirectional"))
      (node (ref "X3") (pin "3") (pinfunction "S_3") (pintype "passive"))
    )
    (net (code "75") (name "RS485-Y") (class "Default")
      (node (ref "JP3") (pin "2") (pinfunction "2_2") (pintype "passive"))
      (node (ref "U2") (pin "9") (pinfunction "Y_9") (pintype "bidirectional"))
      (node (ref "X3") (pin "1") (pinfunction "S_1") (pintype "passive"))
    )
    (net (code "76") (name "RS485-Z") (class "Default")
      (node (ref "JP5") (pin "2") (pinfunction "2_2") (pintype "passive"))
      (node (ref "U2") (pin "10") (pinfunction "Z_10") (pintype "bidirectional"))
      (node (ref "X3") (pin "2") (pinfunction "S_2") (pintype "passive"))
    )
    (net (code "77") (name "RXD") (class "Default")
      (node (ref "R17") (pin "2") (pinfunction "2_2") (pintype "passive"))
      (node (ref "U1") (pin "30") (pinfunction "PD0(RXD)_30") (pintype "bidirectional"))
      (node (ref "U2") (pin "2") (pinfunction "R_2") (pintype "bidirectional"))
      (node (ref "X3") (pin "5") (pinfunction "S_5") (pintype "passive"))
    )
    (net (code "78") (name "SCK") (class "Default")
      (node (ref "J1") (pin "3") (pinfunction "3_3") (pintype "passive"))
      (node (ref "U1") (pin "17") (pinfunction "PB5(SCK)_17") (pintype "bidirectional"))
    )
    (net (code "79") (name "STATUS") (class "Default")
      (node (ref "LED17") (pin "C") (pinfunction "C_C") (pintype "passive"))
      (node (ref "U1") (pin "2") (pinfunction "PD4(XCK/T0)_2") (pintype "bidirectional"))
    )
    (net (code "80") (name "TXD") (class "Default")
      (node (ref "R23") (pin "2") (pinfunction "2_2") (pintype "passive"))
      (node (ref "U1") (pin "31") (pinfunction "PD1(TXD)_31") (pintype "bidirectional"))
      (node (ref "U2") (pin "5") (pinfunction "D_5") (pintype "bidirectional"))
      (node (ref "X3") (pin "6") (pinfunction "S_6") (pintype "passive"))
    )
    (net (code "81") (name "VCC") (class "Default")
      (node (ref "C1") (pin "+") (pinfunction "+_+") (pintype "passive"))
      (node (ref "C2") (pin "1") (pinfunction "1_1") (pintype "passive"))
      (node (ref "C7") (pin "1") (pinfunction "1_1") (pintype "passive"))
      (node (ref "IC1") (pin "2") (pinfunction "OUT_2") (pintype "passive"))
      (node (ref "IC1") (pin "4") (pinfunction "OUT_4") (pintype "passive"))
      (node (ref "J1") (pin "2") (pinfunction "2_2") (pintype "passive"))
      (node (ref "R1") (pin "2") (pinfunction "2_2") (pintype "passive"))
      (node (ref "R10") (pin "2") (pinfunction "2_2") (pintype "passive"))
      (node (ref "R11") (pin "2") (pinfunction "2_2") (pintype "passive"))
      (node (ref "R12") (pin "2") (pinfunction "2_2") (pintype "passive"))
      (node (ref "R13") (pin "2") (pinfunction "2_2") (pintype "passive"))
      (node (ref "R14") (pin "2") (pinfunction "2_2") (pintype "passive"))
      (node (ref "R19") (pin "2") (pinfunction "2_2") (pintype "passive"))
      (node (ref "R2") (pin "2") (pinfunction "2_2") (pintype "passive"))
      (node (ref "R20") (pin "2") (pinfunction "2_2") (pintype "passive"))
      (node (ref "R21") (pin "2") (pinfunction "2_2") (pintype "passive"))
      (node (ref "R22") (pin "2") (pinfunction "2_2") (pintype "passive"))
      (node (ref "R3") (pin "2") (pinfunction "2_2") (pintype "passive"))
      (node (ref "R31") (pin "2") (pinfunction "2_2") (pintype "passive"))
      (node (ref "R4") (pin "2") (pinfunction "2_2") (pintype "passive"))
      (node (ref "R5") (pin "2") (pinfunction "2_2") (pintype "passive"))
      (node (ref "R6") (pin "2") (pinfunction "2_2") (pintype "passive"))
      (node (ref "R7") (pin "2") (pinfunction "2_2") (pintype "passive"))
      (node (ref "R8") (pin "2") (pinfunction "2_2") (pintype "passive"))
      (node (ref "R9") (pin "2") (pinfunction "2_2") (pintype "passive"))
      (node (ref "U1") (pin "18") (pinfunction "AVCC_18") (pintype "bidirectional"))
      (node (ref "U1") (pin "4") (pinfunction "VCC_4") (pintype "bidirectional"))
      (node (ref "U1") (pin "6") (pinfunction "VCC_6") (pintype "bidirectional"))
      (node (ref "U2") (pin "14") (pinfunction "VCC_14") (pintype "bidirectional"))
      (node (ref "X3") (pin "9") (pinfunction "S_9") (pintype "passive"))
    )
    (net (code "82") (name "unconnected-(U1-AREF-Pad20)") (class "Default")
      (node (ref "U1") (pin "20") (pinfunction "AREF_20") (pintype "bidirectional"))
    )
    (net (code "83") (name "unconnected-(U2-NC1-Pad1)") (class "Default")
      (node (ref "U2") (pin "1") (pinfunction "NC1_1") (pintype "bidirectional"))
    )
    (net (code "84") (name "unconnected-(U2-NC2-Pad8)") (class "Default")
      (node (ref "U2") (pin "8") (pinfunction "NC2_8") (pintype "bidirectional"))
    )
    (net (code "85") (name "unconnected-(U2-NC3-Pad13)") (class "Default")
      (node (ref "U2") (pin "13") (pinfunction "NC3_13") (pintype "bidirectional"))
    )
  )
)
